# POWER_SUPPLY.net
KiCad netlist of a schematic drawn in Altium Designer
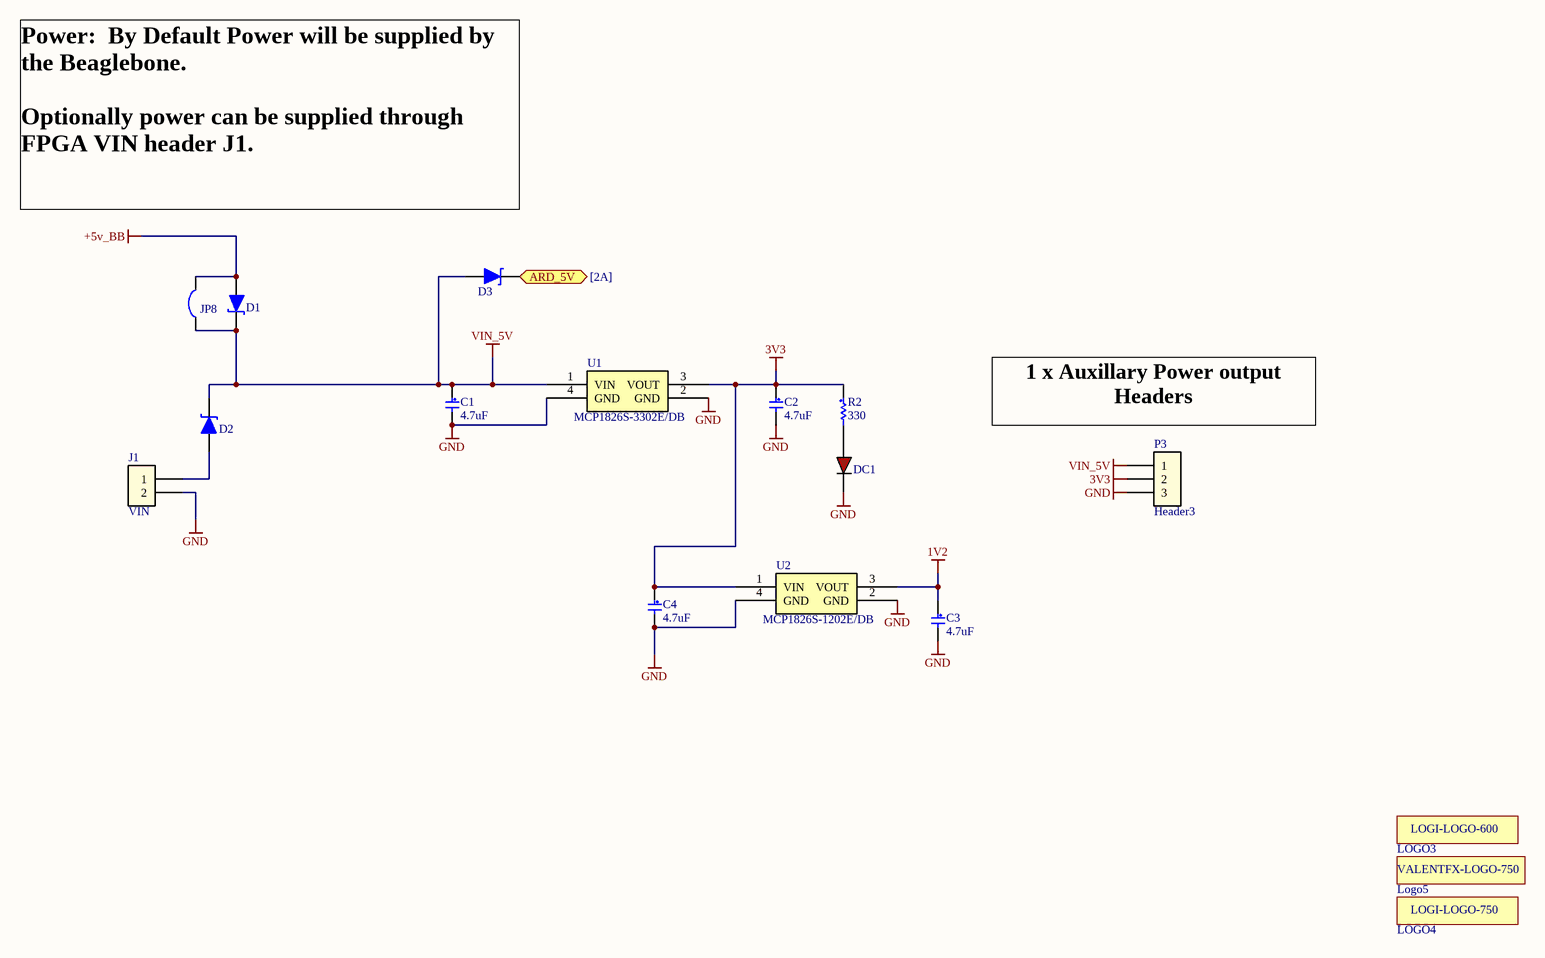
[diagram p0: POWER_SUPPLY.SchDoc]

(export (version "E")
  (design (tool "Eeschema 10.0.6"))
  (components
    (comp (ref "C1")
      (value "4.7uF")
      (footprint "C0603 - Marked")
      (description "4.7uF 6.3volts X5R 10% (MLCC) - SMD/SMT 0603")
      (fields
        (field (name "MANUFACTURER") "Murata Electronics North America")
        (field (name "MANUFACTURER PART NUMBER") "GRM188R60J475KE19D")
      )
      (libsource (lib "mCapacitors") (part "C0603 - GRM188R60J475KE19D"))
    )
    (comp (ref "C2")
      (value "4.7uF")
      (footprint "C0603 - Marked")
      (description "4.7uF 6.3volts X5R 10% (MLCC) - SMD/SMT 0603")
      (fields
        (field (name "MANUFACTURER") "Murata Electronics North America")
        (field (name "MANUFACTURER PART NUMBER") "GRM188R60J475KE19D")
      )
      (libsource (lib "mCapacitors") (part "C0603 - GRM188R60J475KE19D"))
    )
    (comp (ref "C3")
      (value "4.7uF")
      (footprint "C0603 - Marked")
      (description "4.7uF 6.3volts X5R 10% (MLCC) - SMD/SMT 0603")
      (fields
        (field (name "MANUFACTURER") "Murata Electronics North America")
        (field (name "MANUFACTURER PART NUMBER") "GRM188R60J475KE19D")
      )
      (libsource (lib "mCapacitors") (part "C0603 - GRM188R60J475KE19D"))
    )
    (comp (ref "C4")
      (value "4.7uF")
      (footprint "C0603 - Marked")
      (description "4.7uF 6.3volts X5R 10% (MLCC) - SMD/SMT 0603")
      (fields
        (field (name "MANUFACTURER") "Murata Electronics North America")
        (field (name "MANUFACTURER PART NUMBER") "GRM188R60J475KE19D")
      )
      (libsource (lib "mCapacitors") (part "C0603 - GRM188R60J475KE19D"))
    )
    (comp (ref "D1")
      (value "RB161M-20TR")
      (footprint "mdiode:SOD-123")
      (description "DIODE SCHOTTKY 25V 1A SOD123")
      (fields
        (field (name "MANUFACTURER") "Diodes Inc")
        (field (name "MANUFACTURER PART NUMBER") "Rohm Semiconductor")
        (field (name "SOURCE") "Digikey")
      )
      (libsource (lib "mDiode") (part "RB161M-20TR"))
    )
    (comp (ref "D2")
      (value "RB161M-20TR")
      (footprint "mdiode:SOD-123")
      (description "DIODE SCHOTTKY 25V 1A SOD123")
      (fields
        (field (name "MANUFACTURER") "Diodes Inc")
        (field (name "MANUFACTURER PART NUMBER") "Rohm Semiconductor")
        (field (name "SOURCE") "Digikey")
      )
      (libsource (lib "mDiode") (part "RB161M-20TR"))
    )
    (comp (ref "D3")
      (value "RB161M-20TR")
      (footprint "mdiode:SOD-123")
      (description "DIODE SCHOTTKY 25V 1A SOD123")
      (fields
        (field (name "MANUFACTURER") "Diodes Inc")
        (field (name "MANUFACTURER PART NUMBER") "Rohm Semiconductor")
        (field (name "SOURCE") "Digikey")
      )
      (libsource (lib "mDiode") (part "RB161M-20TR"))
    )
    (comp (ref "DC1")
      (value "598-8010-107F")
      (footprint "LED_0603 - RED")
      (description "LED ALINGAP RED CLEAR 0603 SMD")
      (fields (field (name "MANUFACTURER") "Dialight"))
      (libsource (lib "mDiode") (part "LED0603 - 598-8010-107F"))
    )
    (comp (ref "J1")
      (value "VIN")
      (footprint "HEADER_2_40_100 THRU SIP")
      (description "Header 2 pin")
      (libsource (lib "mConnector") (part "Header2"))
    )
    (comp (ref "JP8")
      (value "Solder Jumper")
      (footprint "SOLDER_JUMPER")
      (description "Solder/Configuration Jumper")
      (fields (field (name "MANUFACTURER") "n/a"))
      (libsource (lib "mConnector") (part "Solder Jumper"))
    )
    (comp (ref "LOGO3")
      (value "LOGI-600")
      (footprint "LOGI-600-SILK")
      (libsource (lib "mLogos") (part "LOGI-600"))
    )
    (comp (ref "LOGO4")
      (value "LOGI-750")
      (footprint "LOGI-750-SILK-NB")
      (libsource (lib "mLogos") (part "LOGI-750"))
    )
    (comp (ref "Logo5")
      (value "Valent Logo 750")
      (footprint "VALENTFX_750-SolderMask")
      (libsource (lib "mLogos") (part "Valent Logo 750"))
    )
    (comp (ref "P3")
      (value "Header3")
      (footprint "HEADER_3_40_100 THRU SIP")
      (description "Header  pin")
      (libsource (lib "mConnector") (part "Header3"))
    )
    (comp (ref "R2")
      (value "330")
      (footprint "R0603")
      (description "Thick Film Resistors - SMD 0603 330ohms 5% Tol")
      (fields
        (field (name "MANUFACTURER") "Panasonic")
        (field (name "MANUFACTURER PART NUMBER") "ERJ-3GEYJ331V")
      )
      (libsource (lib "mResistors") (part "R0603 - ERJ-3GEYJ331V"))
    )
    (comp (ref "U1")
      (value "MCP1826S-3302E/DB")
      (footprint "SOT223")
      (description "LDO REG 1A 3.3V SOT223-3")
      (fields (field (name "MANUFACTURER") "Microchip Technology"))
      (libsource (lib "mIC") (part "REG - MCP1826S-3302E/DB"))
    )
    (comp (ref "U2")
      (value "MCP1826S-1202E/DB")
      (footprint "SOT223")
      (description "IC LDO REG 1A 1.2V SOT223-3")
      (fields (field (name "MANUFACTURER") "Microchip Technology"))
      (libsource (lib "eIC") (part "MCP1826S-1202E/DB"))
    )
  )
  (nets
    (net (code "1") (name "+5v_BB") (class "Default")
      (node (ref "D1") (pin "2") (pinfunction "A_2") (pintype "passive"))
      (node (ref "JP8") (pin "1") (pinfunction "1_1") (pintype "passive"))
    )
    (net (code "2") (name "/ARD_5V") (class "Default")
      (node (ref "D3") (pin "1") (pinfunction "C_1") (pintype "passive"))
    )
    (net (code "3") (name "1V2") (class "Default")
      (node (ref "C3") (pin "1") (pinfunction "1_1") (pintype "passive"))
      (node (ref "U2") (pin "3") (pinfunction "VOUT_3") (pintype "passive"))
    )
    (net (code "4") (name "3V3") (class "Default")
      (node (ref "C2") (pin "1") (pinfunction "1_1") (pintype "passive"))
      (node (ref "C4") (pin "1") (pinfunction "1_1") (pintype "passive"))
      (node (ref "P3") (pin "2") (pinfunction "2_2") (pintype "passive"))
      (node (ref "R2") (pin "1") (pinfunction "1_1") (pintype "passive"))
      (node (ref "U1") (pin "3") (pinfunction "VOUT_3") (pintype "passive"))
      (node (ref "U2") (pin "1") (pinfunction "VIN_1") (pintype "passive"))
    )
    (net (code "5") (name "GND") (class "Default")
      (node (ref "C1") (pin "2") (pinfunction "2_2") (pintype "passive"))
      (node (ref "C2") (pin "2") (pinfunction "2_2") (pintype "passive"))
      (node (ref "C3") (pin "2") (pinfunction "2_2") (pintype "passive"))
      (node (ref "C4") (pin "2") (pinfunction "2_2") (pintype "passive"))
      (node (ref "DC1") (pin "C") (pinfunction "C_C") (pintype "passive"))
      (node (ref "J1") (pin "2") (pinfunction "2_2") (pintype "passive"))
      (node (ref "P3") (pin "3") (pinfunction "3_3") (pintype "passive"))
      (node (ref "U1") (pin "2") (pinfunction "GND_2") (pintype "passive"))
      (node (ref "U1") (pin "4") (pinfunction "GND_4") (pintype "passive"))
      (node (ref "U2") (pin "2") (pinfunction "GND_2") (pintype "passive"))
      (node (ref "U2") (pin "4") (pinfunction "GND_4") (pintype "passive"))
    )
    (net (code "6") (name "Net-(D2-A)") (class "Default")
      (node (ref "D2") (pin "2") (pinfunction "A_2") (pintype "passive"))
      (node (ref "J1") (pin "1") (pinfunction "1_1") (pintype "passive"))
    )
    (net (code "7") (name "Net-(DC1-PadA)") (class "Default")
      (node (ref "DC1") (pin "A") (pinfunction "A_A") (pintype "passive"))
      (node (ref "R2") (pin "2") (pinfunction "2_2") (pintype "passive"))
    )
    (net (code "8") (name "VIN_5V") (class "Default")
      (node (ref "C1") (pin "1") (pinfunction "1_1") (pintype "passive"))
      (node (ref "D1") (pin "1") (pinfunction "C_1") (pintype "passive"))
      (node (ref "D2") (pin "1") (pinfunction "C_1") (pintype "passive"))
      (node (ref "D3") (pin "2") (pinfunction "A_2") (pintype "passive"))
      (node (ref "JP8") (pin "2") (pinfunction "2_2") (pintype "passive"))
      (node (ref "P3") (pin "1") (pinfunction "1_1") (pintype "passive"))
      (node (ref "U1") (pin "1") (pinfunction "VIN_1") (pintype "passive"))
    )
  )
)
